# hallsensor.net
KiCad netlist of a schematic drawn in EAGLE
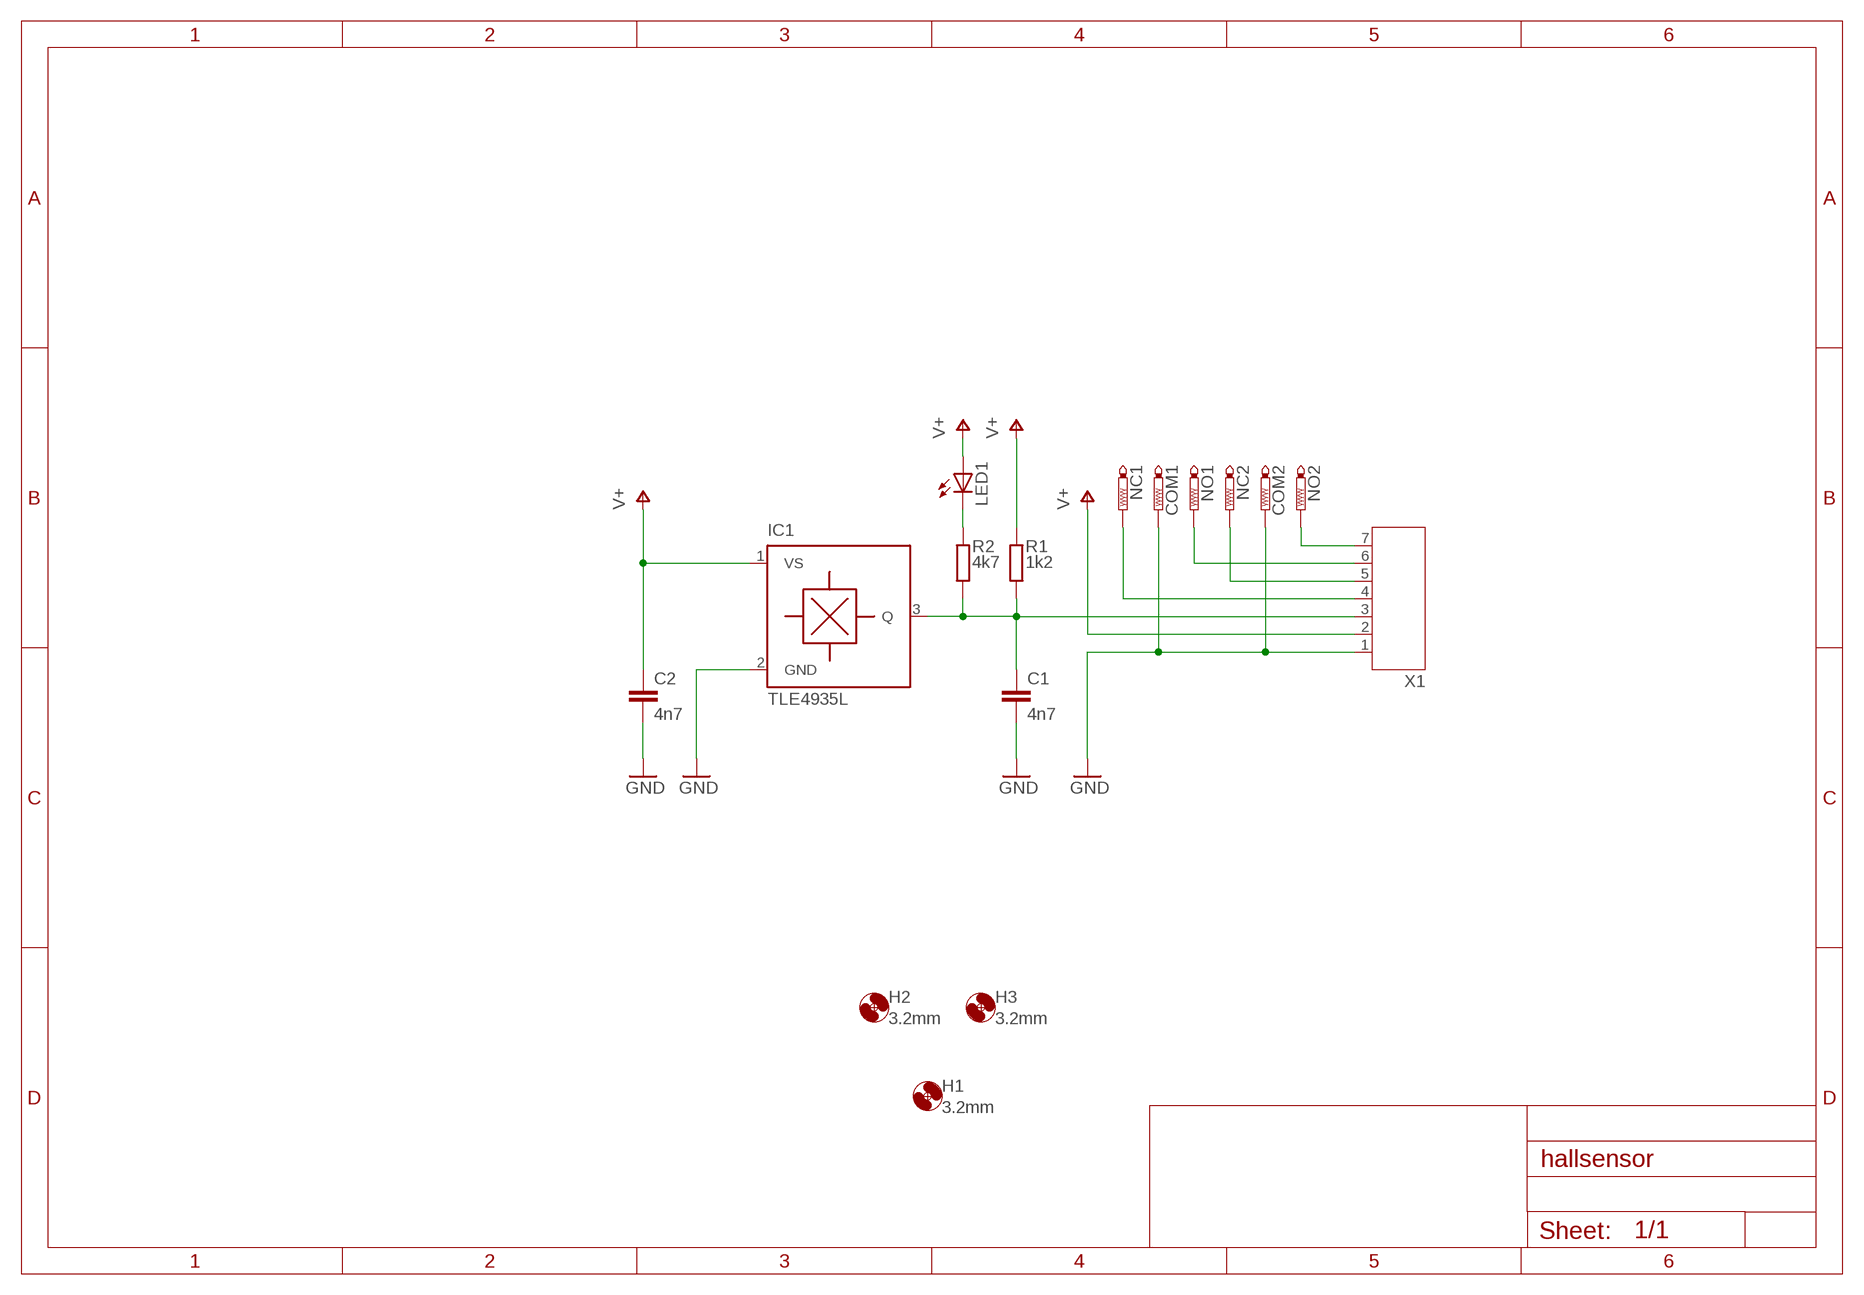
[diagram p0: schematic, sheet 1]

(export (version "E")
  (design (tool "Eeschema 10.0.6"))
  (components
    (comp (ref "C1")
      (value "4n7")
      (footprint "eagle-import:C0805")
      (libsource (lib "eagle-import") (part "C-EUC0805"))
    )
    (comp (ref "C2")
      (value "4n7")
      (footprint "eagle-import:C0805")
      (libsource (lib "eagle-import") (part "C-EUC0805"))
    )
    (comp (ref "COM1")
      (value "PTR1PAD1-13Y")
      (footprint "eagle-import:P1-13Y")
      (libsource (lib "eagle-import") (part "PTR1PAD1-13Y"))
    )
    (comp (ref "COM2")
      (value "PTR1PAD1-13Y")
      (footprint "eagle-import:P1-13Y")
      (libsource (lib "eagle-import") (part "PTR1PAD1-13Y"))
    )
    (comp (ref "H1")
      (value "3.2mm")
      (footprint "eagle-import:3,2")
      (libsource (lib "eagle-import") (part "MOUNT-HOLE3.2"))
    )
    (comp (ref "H2")
      (value "3.2mm")
      (footprint "eagle-import:3,2")
      (libsource (lib "eagle-import") (part "MOUNT-HOLE3.2"))
    )
    (comp (ref "H3")
      (value "3.2mm")
      (footprint "eagle-import:3,2")
      (libsource (lib "eagle-import") (part "MOUNT-HOLE3.2"))
    )
    (comp (ref "IC1")
      (value "TLE4935L")
      (footprint "eagle-import:PG-SSO-3-2")
      (libsource (lib "eagle-import") (part "TLE49X5L"))
    )
    (comp (ref "LED1")
      (value "LED3MM")
      (footprint "eagle-import:LED3MM")
      (libsource (lib "eagle-import") (part "LED3MM"))
    )
    (comp (ref "NC1")
      (value "PTR1PAD1-13Y")
      (footprint "eagle-import:P1-13Y")
      (libsource (lib "eagle-import") (part "PTR1PAD1-13Y"))
    )
    (comp (ref "NC2")
      (value "PTR1PAD1-13Y")
      (footprint "eagle-import:P1-13Y")
      (libsource (lib "eagle-import") (part "PTR1PAD1-13Y"))
    )
    (comp (ref "NO1")
      (value "PTR1PAD1-13Y")
      (footprint "eagle-import:P1-13Y")
      (libsource (lib "eagle-import") (part "PTR1PAD1-13Y"))
    )
    (comp (ref "NO2")
      (value "PTR1PAD1-13Y")
      (footprint "eagle-import:P1-13Y")
      (libsource (lib "eagle-import") (part "PTR1PAD1-13Y"))
    )
    (comp (ref "R1")
      (value "1k2")
      (footprint "eagle-import:R0805")
      (libsource (lib "eagle-import") (part "R-EU_R0805"))
    )
    (comp (ref "R2")
      (value "4k7")
      (footprint "eagle-import:R0805")
      (libsource (lib "eagle-import") (part "R-EU_R0805"))
    )
    (comp (ref "X1")
      (value "JST-PH7")
      (footprint "eagle-import:JST-PH7")
      (libsource (lib "eagle-import") (part "JST-PH7"))
    )
  )
  (nets
    (net (code "1") (name "GND") (class "Default")
      (node (ref "C1") (pin "2") (pinfunction "2_2") (pintype "passive"))
      (node (ref "C2") (pin "2") (pinfunction "2_2") (pintype "passive"))
      (node (ref "COM1") (pin "1") (pinfunction "TP_1") (pintype "input"))
      (node (ref "COM2") (pin "1") (pinfunction "TP_1") (pintype "input"))
      (node (ref "IC1") (pin "2") (pinfunction "GND_2") (pintype "power_in"))
      (node (ref "X1") (pin "1") (pinfunction "1_1") (pintype "passive"))
    )
    (net (code "2") (name "Net-(IC1-Q)") (class "Default")
      (node (ref "C1") (pin "1") (pinfunction "1_1") (pintype "passive"))
      (node (ref "IC1") (pin "3") (pinfunction "Q_3") (pintype "output"))
      (node (ref "R1") (pin "1") (pinfunction "1_1") (pintype "passive"))
      (node (ref "R2") (pin "1") (pinfunction "1_1") (pintype "passive"))
      (node (ref "X1") (pin "3") (pinfunction "3_3") (pintype "passive"))
    )
    (net (code "3") (name "Net-(LED1-C)") (class "Default")
      (node (ref "LED1") (pin "K") (pinfunction "C_K") (pintype "passive"))
      (node (ref "R2") (pin "2") (pinfunction "2_2") (pintype "passive"))
    )
    (net (code "4") (name "Net-(NC1-TP)") (class "Default")
      (node (ref "NC1") (pin "1") (pinfunction "TP_1") (pintype "input"))
      (node (ref "X1") (pin "4") (pinfunction "4_4") (pintype "passive"))
    )
    (net (code "5") (name "Net-(NC2-TP)") (class "Default")
      (node (ref "NC2") (pin "1") (pinfunction "TP_1") (pintype "input"))
      (node (ref "X1") (pin "5") (pinfunction "5_5") (pintype "passive"))
    )
    (net (code "6") (name "Net-(NO1-TP)") (class "Default")
      (node (ref "NO1") (pin "1") (pinfunction "TP_1") (pintype "input"))
      (node (ref "X1") (pin "6") (pinfunction "6_6") (pintype "passive"))
    )
    (net (code "7") (name "Net-(NO2-TP)") (class "Default")
      (node (ref "NO2") (pin "1") (pinfunction "TP_1") (pintype "input"))
      (node (ref "X1") (pin "7") (pinfunction "7_7") (pintype "passive"))
    )
    (net (code "8") (name "V+") (class "Default")
      (node (ref "C2") (pin "1") (pinfunction "1_1") (pintype "passive"))
      (node (ref "IC1") (pin "1") (pinfunction "VS_1") (pintype "input"))
      (node (ref "LED1") (pin "A") (pinfunction "A_A") (pintype "passive"))
      (node (ref "R1") (pin "2") (pinfunction "2_2") (pintype "passive"))
      (node (ref "X1") (pin "2") (pinfunction "2_2") (pintype "passive"))
    )
  )
)
